# ECEN404_Team54_V2.net
KiCad netlist of a schematic drawn in Altium Designer
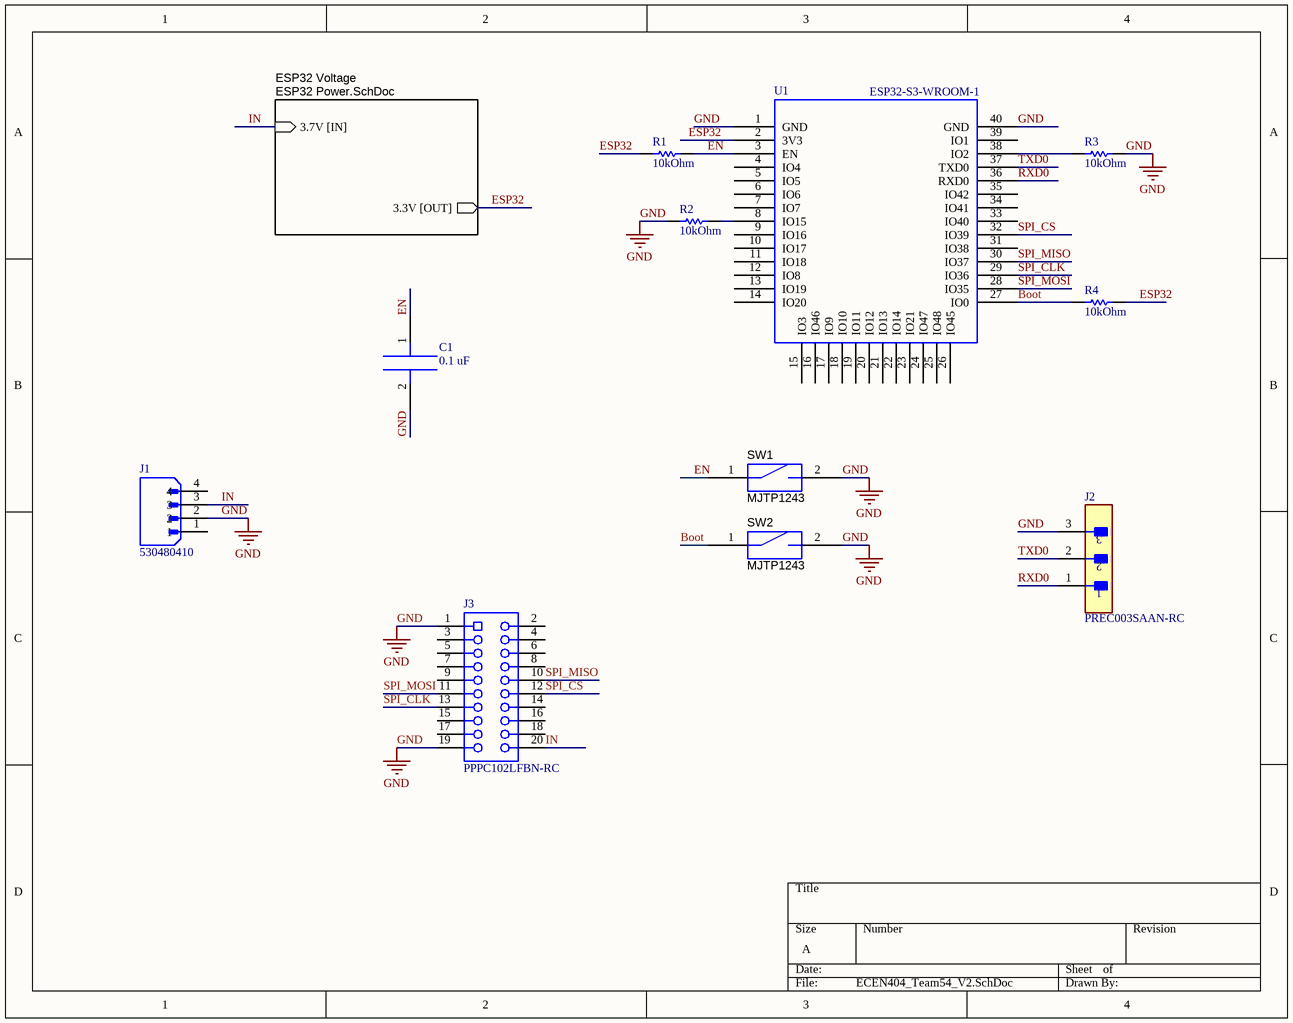
[diagram p0: ECEN404_Team54_V2.SchDoc]

(export (version "E")
  (design (tool "Eeschema 10.0.6"))
  (components
    (comp (ref "C1")
      (value "0.1 uF")
      (footprint "1206 Capacitor")
      (description "0.1 µF ±10% 6.3V Ceramic Capacitor X7R 1206 (3216 Metric)")
      (fields (field (name "Comment") "GMC31X7R104K6R3NT"))
      (libsource (lib "Team54_Parts") (part "GMC31X7R104K6R3NT"))
    )
    (comp (ref "J1")
      (value "530480410")
      (footprint "MOLEX_530480410")
      (libsource (lib "530480410") (part "530480410"))
    )
    (comp (ref "J2")
      (value "PREC003SAAN-RC")
      (footprint "FP-PREC003SAAN-RC-MFG")
      (description "PREC003SAAN-RC Conn Header Vert 3POS 2.54MM")
      (libsource (lib "Altium Content Vault") (part "0d3f023dd272f625e17a2be33dea85f"))
    )
    (comp (ref "J3")
      (value "PPPC102LFBN-RC")
      (footprint "SLIN-PPPC102LFBN-RC_V")
      (libsource (lib "Altium Content Vault") (part "CN-2P-F-R20"))
    )
    (comp (ref "R1")
      (value "10kOhm")
      (footprint "RESC3216X70X50LL05T20")
      (description "ERJ-8ENF1002V")
      (fields (field (name "MANUFACTURER") "Panasonic"))
      (libsource (lib "Altium Content Vault") (part "RES"))
    )
    (comp (ref "R2")
      (value "10kOhm")
      (footprint "RESC3216X70X50LL05T20")
      (description "ERJ-8ENF1002V")
      (fields (field (name "MANUFACTURER") "Panasonic"))
      (libsource (lib "Altium Content Vault") (part "RES"))
    )
    (comp (ref "R3")
      (value "10kOhm")
      (footprint "RESC3216X70X50LL05T20")
      (description "ERJ-8ENF1002V")
      (fields (field (name "MANUFACTURER") "Panasonic"))
      (libsource (lib "Altium Content Vault") (part "RES"))
    )
    (comp (ref "R4")
      (value "10kOhm")
      (footprint "RESC3216X70X50LL05T20")
      (description "ERJ-8ENF1002V")
      (fields (field (name "MANUFACTURER") "Panasonic"))
      (libsource (lib "Altium Content Vault") (part "RES"))
    )
    (comp (ref "SW1")
      (value "MJTP1243")
      (footprint "MJTP1243")
      (description "Tactile Switch SPST-NO Top Actuated Through Hole")
      (libsource (lib "Team54_Parts") (part "MJTP1243"))
    )
    (comp (ref "SW2")
      (value "MJTP1243")
      (footprint "MJTP1243")
      (description "Tactile Switch SPST-NO Top Actuated Through Hole")
      (libsource (lib "Team54_Parts") (part "MJTP1243"))
    )
    (comp (ref "U1")
      (value "ESP32-S3-WROOM-1")
      (footprint "ESP32-WROOM1")
      (description "RF TXRX MOD BT WIFI PCB TH SMD")
      (libsource (lib "Team54_Parts") (part "ESP32-WROOM1"))
    )
  )
  (nets
    (net (code "1") (name "/Boot") (class "Default")
      (node (ref "R4") (pin "1") (pinfunction "1_1") (pintype "passive"))
      (node (ref "SW2") (pin "1") (pinfunction "GND_1") (pintype "passive"))
      (node (ref "U1") (pin "27") (pinfunction "IO0_27") (pintype "passive"))
    )
    (net (code "2") (name "/EN") (class "Default")
      (node (ref "C1") (pin "1") (pinfunction "1_1") (pintype "passive"))
      (node (ref "R1") (pin "2") (pinfunction "2_2") (pintype "passive"))
      (node (ref "SW1") (pin "1") (pinfunction "GND_1") (pintype "passive"))
      (node (ref "U1") (pin "3") (pinfunction "EN_3") (pintype "passive"))
    )
    (net (code "3") (name "/ESP32") (class "Default")
      (node (ref "R1") (pin "1") (pinfunction "1_1") (pintype "passive"))
      (node (ref "R4") (pin "2") (pinfunction "2_2") (pintype "passive"))
      (node (ref "U1") (pin "2") (pinfunction "3V3_2") (pintype "passive"))
    )
    (net (code "4") (name "/IN") (class "Default")
      (node (ref "J1") (pin "3") (pinfunction "3_3") (pintype "passive"))
      (node (ref "J3") (pin "20") (pinfunction "20_20") (pintype "passive"))
    )
    (net (code "5") (name "/RXD0") (class "Default")
      (node (ref "J2") (pin "1") (pinfunction "1_1") (pintype "passive"))
      (node (ref "U1") (pin "36") (pinfunction "RXD0_36") (pintype "passive"))
    )
    (net (code "6") (name "/SPI_CLK") (class "Default")
      (node (ref "J3") (pin "13") (pinfunction "13_13") (pintype "passive"))
      (node (ref "U1") (pin "29") (pinfunction "IO36_29") (pintype "passive"))
    )
    (net (code "7") (name "/SPI_CS") (class "Default")
      (node (ref "J3") (pin "12") (pinfunction "12_12") (pintype "passive"))
      (node (ref "U1") (pin "32") (pinfunction "IO39_32") (pintype "passive"))
    )
    (net (code "8") (name "/SPI_MISO") (class "Default")
      (node (ref "J3") (pin "10") (pinfunction "10_10") (pintype "passive"))
      (node (ref "U1") (pin "30") (pinfunction "IO37_30") (pintype "passive"))
    )
    (net (code "9") (name "/SPI_MOSI") (class "Default")
      (node (ref "J3") (pin "11") (pinfunction "11_11") (pintype "passive"))
      (node (ref "U1") (pin "28") (pinfunction "IO35_28") (pintype "passive"))
    )
    (net (code "10") (name "/TXD0") (class "Default")
      (node (ref "J2") (pin "2") (pinfunction "2_2") (pintype "passive"))
      (node (ref "U1") (pin "37") (pinfunction "TXD0_37") (pintype "passive"))
    )
    (net (code "11") (name "GND") (class "Default")
      (node (ref "C1") (pin "2") (pinfunction "2_2") (pintype "passive"))
      (node (ref "J1") (pin "2") (pinfunction "2_2") (pintype "passive"))
      (node (ref "J2") (pin "3") (pinfunction "3_3") (pintype "passive"))
      (node (ref "J3") (pin "1") (pinfunction "1_1") (pintype "passive"))
      (node (ref "J3") (pin "19") (pinfunction "19_19") (pintype "passive"))
      (node (ref "R2") (pin "1") (pinfunction "1_1") (pintype "passive"))
      (node (ref "R3") (pin "2") (pinfunction "2_2") (pintype "passive"))
      (node (ref "SW1") (pin "2") (pinfunction "1_2") (pintype "passive"))
      (node (ref "SW2") (pin "2") (pinfunction "1_2") (pintype "passive"))
      (node (ref "U1") (pin "1") (pinfunction "GND_1") (pintype "passive"))
      (node (ref "U1") (pin "40") (pinfunction "GND_40") (pintype "passive"))
    )
    (net (code "12") (name "Net-(U1-IO2)") (class "Default")
      (node (ref "R3") (pin "1") (pinfunction "1_1") (pintype "passive"))
      (node (ref "U1") (pin "38") (pinfunction "IO2_38") (pintype "passive"))
    )
    (net (code "13") (name "Net-(U1-IO15)") (class "Default")
      (node (ref "R2") (pin "2") (pinfunction "2_2") (pintype "passive"))
      (node (ref "U1") (pin "8") (pinfunction "IO15_8") (pintype "passive"))
    )
    (net (code "14") (name "unconnected-(J1-Pad1)") (class "Default")
      (node (ref "J1") (pin "1") (pinfunction "1_1") (pintype "passive"))
    )
    (net (code "15") (name "unconnected-(J1-Pad4)") (class "Default")
      (node (ref "J1") (pin "4") (pinfunction "4_4") (pintype "passive"))
    )
    (net (code "16") (name "unconnected-(J3-Pad2)") (class "Default")
      (node (ref "J3") (pin "2") (pinfunction "2_2") (pintype "passive"))
    )
    (net (code "17") (name "unconnected-(J3-Pad3)") (class "Default")
      (node (ref "J3") (pin "3") (pinfunction "3_3") (pintype "passive"))
    )
    (net (code "18") (name "unconnected-(J3-Pad4)") (class "Default")
      (node (ref "J3") (pin "4") (pinfunction "4_4") (pintype "passive"))
    )
    (net (code "19") (name "unconnected-(J3-Pad5)") (class "Default")
      (node (ref "J3") (pin "5") (pinfunction "5_5") (pintype "passive"))
    )
    (net (code "20") (name "unconnected-(J3-Pad6)") (class "Default")
      (node (ref "J3") (pin "6") (pinfunction "6_6") (pintype "passive"))
    )
    (net (code "21") (name "unconnected-(J3-Pad7)") (class "Default")
      (node (ref "J3") (pin "7") (pinfunction "7_7") (pintype "passive"))
    )
    (net (code "22") (name "unconnected-(J3-Pad8)") (class "Default")
      (node (ref "J3") (pin "8") (pinfunction "8_8") (pintype "passive"))
    )
    (net (code "23") (name "unconnected-(J3-Pad9)") (class "Default")
      (node (ref "J3") (pin "9") (pinfunction "9_9") (pintype "passive"))
    )
    (net (code "24") (name "unconnected-(J3-Pad14)") (class "Default")
      (node (ref "J3") (pin "14") (pinfunction "14_14") (pintype "passive"))
    )
    (net (code "25") (name "unconnected-(J3-Pad15)") (class "Default")
      (node (ref "J3") (pin "15") (pinfunction "15_15") (pintype "passive"))
    )
    (net (code "26") (name "unconnected-(J3-Pad16)") (class "Default")
      (node (ref "J3") (pin "16") (pinfunction "16_16") (pintype "passive"))
    )
    (net (code "27") (name "unconnected-(J3-Pad17)") (class "Default")
      (node (ref "J3") (pin "17") (pinfunction "17_17") (pintype "passive"))
    )
    (net (code "28") (name "unconnected-(J3-Pad18)") (class "Default")
      (node (ref "J3") (pin "18") (pinfunction "18_18") (pintype "passive"))
    )
    (net (code "29") (name "unconnected-(U1-IO1-Pad39)") (class "Default")
      (node (ref "U1") (pin "39") (pinfunction "IO1_39") (pintype "passive"))
    )
    (net (code "30") (name "unconnected-(U1-IO3-Pad15)") (class "Default")
      (node (ref "U1") (pin "15") (pinfunction "IO3_15") (pintype "passive"))
    )
    (net (code "31") (name "unconnected-(U1-IO4-Pad4)") (class "Default")
      (node (ref "U1") (pin "4") (pinfunction "IO4_4") (pintype "passive"))
    )
    (net (code "32") (name "unconnected-(U1-IO5-Pad5)") (class "Default")
      (node (ref "U1") (pin "5") (pinfunction "IO5_5") (pintype "passive"))
    )
    (net (code "33") (name "unconnected-(U1-IO6-Pad6)") (class "Default")
      (node (ref "U1") (pin "6") (pinfunction "IO6_6") (pintype "passive"))
    )
    (net (code "34") (name "unconnected-(U1-IO7-Pad7)") (class "Default")
      (node (ref "U1") (pin "7") (pinfunction "IO7_7") (pintype "passive"))
    )
    (net (code "35") (name "unconnected-(U1-IO8-Pad12)") (class "Default")
      (node (ref "U1") (pin "12") (pinfunction "IO8_12") (pintype "passive"))
    )
    (net (code "36") (name "unconnected-(U1-IO9-Pad17)") (class "Default")
      (node (ref "U1") (pin "17") (pinfunction "IO9_17") (pintype "passive"))
    )
    (net (code "37") (name "unconnected-(U1-IO10-Pad18)") (class "Default")
      (node (ref "U1") (pin "18") (pinfunction "IO10_18") (pintype "passive"))
    )
    (net (code "38") (name "unconnected-(U1-IO11-Pad19)") (class "Default")
      (node (ref "U1") (pin "19") (pinfunction "IO11_19") (pintype "passive"))
    )
    (net (code "39") (name "unconnected-(U1-IO12-Pad20)") (class "Default")
      (node (ref "U1") (pin "20") (pinfunction "IO12_20") (pintype "passive"))
    )
    (net (code "40") (name "unconnected-(U1-IO13-Pad21)") (class "Default")
      (node (ref "U1") (pin "21") (pinfunction "IO13_21") (pintype "passive"))
    )
    (net (code "41") (name "unconnected-(U1-IO14-Pad22)") (class "Default")
      (node (ref "U1") (pin "22") (pinfunction "IO14_22") (pintype "passive"))
    )
    (net (code "42") (name "unconnected-(U1-IO16-Pad9)") (class "Default")
      (node (ref "U1") (pin "9") (pinfunction "IO16_9") (pintype "passive"))
    )
    (net (code "43") (name "unconnected-(U1-IO17-Pad10)") (class "Default")
      (node (ref "U1") (pin "10") (pinfunction "IO17_10") (pintype "passive"))
    )
    (net (code "44") (name "unconnected-(U1-IO18-Pad11)") (class "Default")
      (node (ref "U1") (pin "11") (pinfunction "IO18_11") (pintype "passive"))
    )
    (net (code "45") (name "unconnected-(U1-IO19-Pad13)") (class "Default")
      (node (ref "U1") (pin "13") (pinfunction "IO19_13") (pintype "passive"))
    )
    (net (code "46") (name "unconnected-(U1-IO20-Pad14)") (class "Default")
      (node (ref "U1") (pin "14") (pinfunction "IO20_14") (pintype "passive"))
    )
    (net (code "47") (name "unconnected-(U1-IO21-Pad23)") (class "Default")
      (node (ref "U1") (pin "23") (pinfunction "IO21_23") (pintype "passive"))
    )
    (net (code "48") (name "unconnected-(U1-IO38-Pad31)") (class "Default")
      (node (ref "U1") (pin "31") (pinfunction "IO38_31") (pintype "passive"))
    )
    (net (code "49") (name "unconnected-(U1-IO40-Pad33)") (class "Default")
      (node (ref "U1") (pin "33") (pinfunction "IO40_33") (pintype "passive"))
    )
    (net (code "50") (name "unconnected-(U1-IO41-Pad34)") (class "Default")
      (node (ref "U1") (pin "34") (pinfunction "IO41_34") (pintype "passive"))
    )
    (net (code "51") (name "unconnected-(U1-IO42-Pad35)") (class "Default")
      (node (ref "U1") (pin "35") (pinfunction "IO42_35") (pintype "passive"))
    )
    (net (code "52") (name "unconnected-(U1-IO45-Pad26)") (class "Default")
      (node (ref "U1") (pin "26") (pinfunction "IO45_26") (pintype "passive"))
    )
    (net (code "53") (name "unconnected-(U1-IO46-Pad16)") (class "Default")
      (node (ref "U1") (pin "16") (pinfunction "IO46_16") (pintype "passive"))
    )
    (net (code "54") (name "unconnected-(U1-IO47-Pad24)") (class "Default")
      (node (ref "U1") (pin "24") (pinfunction "IO47_24") (pintype "passive"))
    )
    (net (code "55") (name "unconnected-(U1-IO48-Pad25)") (class "Default")
      (node (ref "U1") (pin "25") (pinfunction "IO48_25") (pintype "passive"))
    )
  )
)
